# relay.net
KiCad netlist of a schematic drawn in Altium Designer
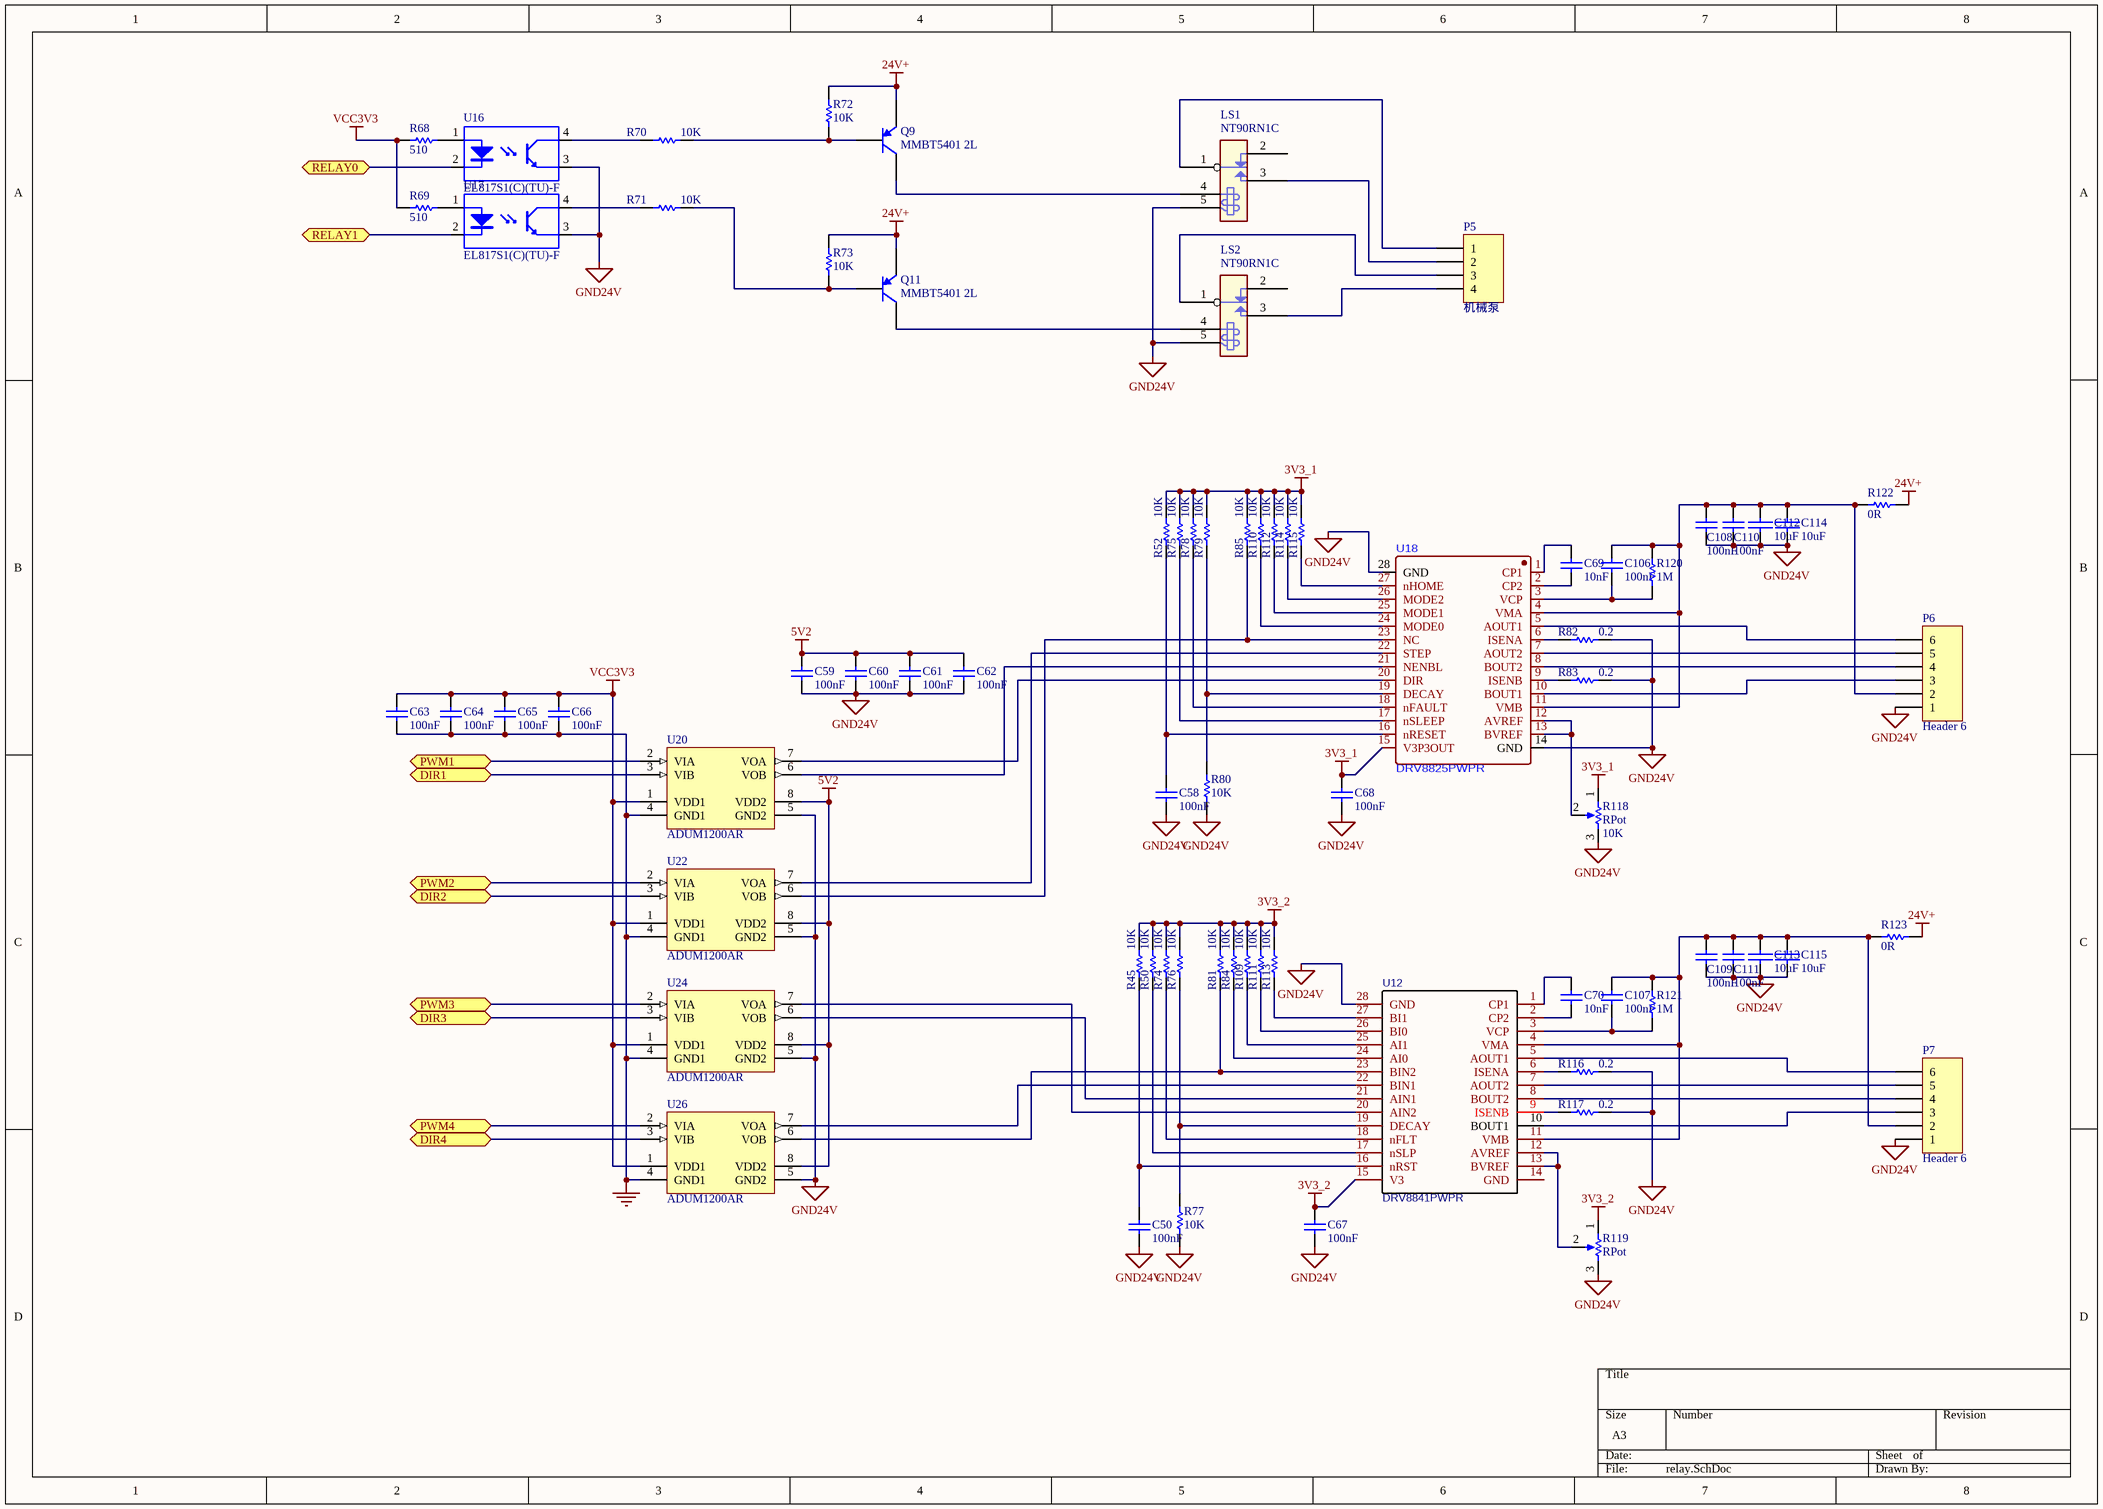
[diagram p0: relay.SchDoc]

(export (version "E")
  (design (tool "Eeschema 10.0.6"))
  (components
    (comp (ref "C50")
      (value "100nF")
      (footprint "0805_C")
      (description "贴片电容")
      (libsource (lib "Miscellaneous Devices LC") (part "0805 100nF(104) 10% 50V"))
    )
    (comp (ref "C58")
      (value "100nF")
      (footprint "0805_C")
      (description "贴片电容")
      (libsource (lib "Miscellaneous Devices LC") (part "0805 100nF(104) 10% 50V"))
    )
    (comp (ref "C59")
      (value "100nF")
      (footprint "0805_C")
      (description "贴片电容")
      (libsource (lib "Miscellaneous Devices LC") (part "0805 100nF(104) 10% 50V"))
    )
    (comp (ref "C60")
      (value "100nF")
      (footprint "0805_C")
      (description "贴片电容")
      (libsource (lib "Miscellaneous Devices LC") (part "0805 100nF(104) 10% 50V"))
    )
    (comp (ref "C61")
      (value "100nF")
      (footprint "0805_C")
      (description "贴片电容")
      (libsource (lib "Miscellaneous Devices LC") (part "0805 100nF(104) 10% 50V"))
    )
    (comp (ref "C62")
      (value "100nF")
      (footprint "0805_C")
      (description "贴片电容")
      (libsource (lib "Miscellaneous Devices LC") (part "0805 100nF(104) 10% 50V"))
    )
    (comp (ref "C63")
      (value "100nF")
      (footprint "0805_C")
      (description "贴片电容")
      (libsource (lib "Miscellaneous Devices LC") (part "0805 100nF(104) 10% 50V"))
    )
    (comp (ref "C64")
      (value "100nF")
      (footprint "0805_C")
      (description "贴片电容")
      (libsource (lib "Miscellaneous Devices LC") (part "0805 100nF(104) 10% 50V"))
    )
    (comp (ref "C65")
      (value "100nF")
      (footprint "0805_C")
      (description "贴片电容")
      (libsource (lib "Miscellaneous Devices LC") (part "0805 100nF(104) 10% 50V"))
    )
    (comp (ref "C66")
      (value "100nF")
      (footprint "0805_C")
      (description "贴片电容")
      (libsource (lib "Miscellaneous Devices LC") (part "0805 100nF(104) 10% 50V"))
    )
    (comp (ref "C67")
      (value "100nF")
      (footprint "0805_C")
      (description "贴片电容")
      (libsource (lib "Miscellaneous Devices LC") (part "0805 100nF(104) 10% 50V"))
    )
    (comp (ref "C68")
      (value "100nF")
      (footprint "0805_C")
      (description "贴片电容")
      (libsource (lib "Miscellaneous Devices LC") (part "0805 100nF(104) 10% 50V"))
    )
    (comp (ref "C69")
      (value "10nF")
      (footprint "0805_C")
      (description "贴片电容")
      (libsource (lib "Miscellaneous Devices LC") (part "0805 100nF(104) 10% 50V"))
    )
    (comp (ref "C70")
      (value "10nF")
      (footprint "0805_C")
      (description "贴片电容")
      (libsource (lib "Miscellaneous Devices LC") (part "0805 100nF(104) 10% 50V"))
    )
    (comp (ref "C106")
      (value "100nF")
      (footprint "0805_C")
      (description "贴片电容")
      (libsource (lib "Miscellaneous Devices LC") (part "0805 100nF(104) 10% 50V"))
    )
    (comp (ref "C107")
      (value "100nF")
      (footprint "0805_C")
      (description "贴片电容")
      (libsource (lib "Miscellaneous Devices LC") (part "0805 100nF(104) 10% 50V"))
    )
    (comp (ref "C108")
      (value "100nF")
      (footprint "0805_C")
      (description "贴片电容")
      (libsource (lib "Miscellaneous Devices LC") (part "0805 100nF(104) 10% 50V"))
    )
    (comp (ref "C109")
      (value "100nF")
      (footprint "0805_C")
      (description "贴片电容")
      (libsource (lib "Miscellaneous Devices LC") (part "0805 100nF(104) 10% 50V"))
    )
    (comp (ref "C110")
      (value "100nF")
      (footprint "0805_C")
      (description "贴片电容")
      (libsource (lib "Miscellaneous Devices LC") (part "0805 100nF(104) 10% 50V"))
    )
    (comp (ref "C111")
      (value "100nF")
      (footprint "0805_C")
      (description "贴片电容")
      (libsource (lib "Miscellaneous Devices LC") (part "0805 100nF(104) 10% 50V"))
    )
    (comp (ref "C112")
      (value "10uF")
      (footprint "0805_C")
      (description "Capacitor")
      (libsource (lib "*") (part "CC"))
    )
    (comp (ref "C113")
      (value "10uF")
      (footprint "0805_C")
      (description "Capacitor")
      (libsource (lib "*") (part "CC"))
    )
    (comp (ref "C114")
      (value "10uF")
      (footprint "0805_C")
      (description "Capacitor")
      (libsource (lib "*") (part "CC"))
    )
    (comp (ref "C115")
      (value "10uF")
      (footprint "0805_C")
      (description "Capacitor")
      (libsource (lib "*") (part "CC"))
    )
    (comp (ref "LS1") (value "NT90RN1C") (libsource (lib "Devices") (part "NT90RN1C")))
    (comp (ref "LS2") (value "NT90RN1C") (libsource (lib "Devices") (part "NT90RN1C")))
    (comp (ref "P5")
      (value "机械泵")
      (footprint "MSTBV 2.5/4-G-5.08")
      (description "Header, 4-Pin, Right Angle")
      (fields (field (name "PUBLISHER") "Altium Limited"))
      (libsource (lib "Miscellaneous Connectors") (part "Header 4H"))
    )
    (comp (ref "P6")
      (value "Header 6")
      (footprint "MC1.5/6-ST-3.81")
      (description "Header, 6-Pin")
      (fields (field (name "PUBLISHER") "Altium Limited"))
      (libsource (lib "Miscellaneous Connectors") (part "Header 6"))
    )
    (comp (ref "P7")
      (value "Header 6")
      (footprint "MC1.5/6-ST-3.81")
      (description "Header, 6-Pin")
      (fields (field (name "PUBLISHER") "Altium Limited"))
      (libsource (lib "Miscellaneous Connectors") (part "Header 6"))
    )
    (comp (ref "Q9")
      (value "MMBT5401 2L")
      (footprint "SOT-23(SOT-23-3)")
      (description "三极管")
      (libsource (lib "Miscellaneous Devices LC") (part "SOT-23 MMBT5401 2L"))
    )
    (comp (ref "Q11")
      (value "MMBT5401 2L")
      (footprint "SOT-23(SOT-23-3)")
      (description "三极管")
      (libsource (lib "Miscellaneous Devices LC") (part "SOT-23 MMBT5401 2L"))
    )
    (comp (ref "R45")
      (value "10K")
      (footprint "0805_R")
      (description "Resistor")
      (fields (field (name "PUBLISHER") "Altium Limited"))
      (libsource (lib "Miscellaneous Devices") (part "Res1"))
    )
    (comp (ref "R50")
      (value "10K")
      (footprint "0805_R")
      (description "Resistor")
      (fields (field (name "PUBLISHER") "Altium Limited"))
      (libsource (lib "Miscellaneous Devices") (part "Res1"))
    )
    (comp (ref "R52")
      (value "10K")
      (footprint "0805_R")
      (description "Resistor")
      (fields (field (name "PUBLISHER") "Altium Limited"))
      (libsource (lib "Miscellaneous Devices") (part "Res1"))
    )
    (comp (ref "R68")
      (value "510")
      (footprint "0805_R")
      (description "Resistor")
      (fields (field (name "PUBLISHER") "Altium Limited"))
      (libsource (lib "Miscellaneous Devices") (part "Res1"))
    )
    (comp (ref "R69")
      (value "510")
      (footprint "0805_R")
      (description "Resistor")
      (fields (field (name "PUBLISHER") "Altium Limited"))
      (libsource (lib "Miscellaneous Devices") (part "Res1"))
    )
    (comp (ref "R70")
      (value "10K")
      (footprint "0805_R")
      (description "Resistor")
      (fields (field (name "PUBLISHER") "Altium Limited"))
      (libsource (lib "Miscellaneous Devices") (part "Res1"))
    )
    (comp (ref "R71")
      (value "10K")
      (footprint "0805_R")
      (description "Resistor")
      (fields (field (name "PUBLISHER") "Altium Limited"))
      (libsource (lib "Miscellaneous Devices") (part "Res1"))
    )
    (comp (ref "R72")
      (value "10K")
      (footprint "0805_R")
      (description "Resistor")
      (fields (field (name "PUBLISHER") "Altium Limited"))
      (libsource (lib "Miscellaneous Devices") (part "Res1"))
    )
    (comp (ref "R73")
      (value "10K")
      (footprint "0805_R")
      (description "Resistor")
      (fields (field (name "PUBLISHER") "Altium Limited"))
      (libsource (lib "Miscellaneous Devices") (part "Res1"))
    )
    (comp (ref "R74")
      (value "10K")
      (footprint "0805_R")
      (description "Resistor")
      (fields (field (name "PUBLISHER") "Altium Limited"))
      (libsource (lib "Miscellaneous Devices") (part "Res1"))
    )
    (comp (ref "R75")
      (value "10K")
      (footprint "0805_R")
      (description "Resistor")
      (fields (field (name "PUBLISHER") "Altium Limited"))
      (libsource (lib "Miscellaneous Devices") (part "Res1"))
    )
    (comp (ref "R76")
      (value "10K")
      (footprint "0805_R")
      (description "Resistor")
      (fields (field (name "PUBLISHER") "Altium Limited"))
      (libsource (lib "Miscellaneous Devices") (part "Res1"))
    )
    (comp (ref "R77")
      (value "10K")
      (footprint "0805_R")
      (description "Resistor")
      (fields (field (name "PUBLISHER") "Altium Limited"))
      (libsource (lib "Miscellaneous Devices") (part "Res1"))
    )
    (comp (ref "R78")
      (value "10K")
      (footprint "0805_R")
      (description "Resistor")
      (fields (field (name "PUBLISHER") "Altium Limited"))
      (libsource (lib "Miscellaneous Devices") (part "Res1"))
    )
    (comp (ref "R79")
      (value "10K")
      (footprint "0805_R")
      (description "Resistor")
      (fields (field (name "PUBLISHER") "Altium Limited"))
      (libsource (lib "Miscellaneous Devices") (part "Res1"))
    )
    (comp (ref "R80")
      (value "10K")
      (footprint "0805_R")
      (description "Resistor")
      (fields (field (name "PUBLISHER") "Altium Limited"))
      (libsource (lib "Miscellaneous Devices") (part "Res1"))
    )
    (comp (ref "R81")
      (value "10K")
      (footprint "0805_R")
      (description "Resistor")
      (fields (field (name "PUBLISHER") "Altium Limited"))
      (libsource (lib "Miscellaneous Devices") (part "Res1"))
    )
    (comp (ref "R82")
      (value "0.2")
      (footprint "R1210")
      (description "Resistor")
      (fields (field (name "PUBLISHER") "Altium Limited"))
      (libsource (lib "Miscellaneous Devices") (part "Res1"))
    )
    (comp (ref "R83")
      (value "0.2")
      (footprint "R1210")
      (description "Resistor")
      (fields (field (name "PUBLISHER") "Altium Limited"))
      (libsource (lib "Miscellaneous Devices") (part "Res1"))
    )
    (comp (ref "R84")
      (value "10K")
      (footprint "0805_R")
      (description "Resistor")
      (fields (field (name "PUBLISHER") "Altium Limited"))
      (libsource (lib "Miscellaneous Devices") (part "Res1"))
    )
    (comp (ref "R85")
      (value "10K")
      (footprint "0805_R")
      (description "Resistor")
      (fields (field (name "PUBLISHER") "Altium Limited"))
      (libsource (lib "Miscellaneous Devices") (part "Res1"))
    )
    (comp (ref "R109")
      (value "10K")
      (footprint "0805_R")
      (description "Resistor")
      (fields (field (name "PUBLISHER") "Altium Limited"))
      (libsource (lib "Miscellaneous Devices") (part "Res1"))
    )
    (comp (ref "R110")
      (value "10K")
      (footprint "0805_R")
      (description "Resistor")
      (fields (field (name "PUBLISHER") "Altium Limited"))
      (libsource (lib "Miscellaneous Devices") (part "Res1"))
    )
    (comp (ref "R111")
      (value "10K")
      (footprint "0805_R")
      (description "Resistor")
      (fields (field (name "PUBLISHER") "Altium Limited"))
      (libsource (lib "Miscellaneous Devices") (part "Res1"))
    )
    (comp (ref "R112")
      (value "10K")
      (footprint "0805_R")
      (description "Resistor")
      (fields (field (name "PUBLISHER") "Altium Limited"))
      (libsource (lib "Miscellaneous Devices") (part "Res1"))
    )
    (comp (ref "R113")
      (value "10K")
      (footprint "0805_R")
      (description "Resistor")
      (fields (field (name "PUBLISHER") "Altium Limited"))
      (libsource (lib "Miscellaneous Devices") (part "Res1"))
    )
    (comp (ref "R114")
      (value "10K")
      (footprint "0805_R")
      (description "Resistor")
      (fields (field (name "PUBLISHER") "Altium Limited"))
      (libsource (lib "Miscellaneous Devices") (part "Res1"))
    )
    (comp (ref "R115")
      (value "10K")
      (footprint "0805_R")
      (description "Resistor")
      (fields (field (name "PUBLISHER") "Altium Limited"))
      (libsource (lib "Miscellaneous Devices") (part "Res1"))
    )
    (comp (ref "R116")
      (value "0.2")
      (footprint "R1210")
      (description "Resistor")
      (fields (field (name "PUBLISHER") "Altium Limited"))
      (libsource (lib "Miscellaneous Devices") (part "Res1"))
    )
    (comp (ref "R117")
      (value "0.2")
      (footprint "R1210")
      (description "Resistor")
      (fields (field (name "PUBLISHER") "Altium Limited"))
      (libsource (lib "Miscellaneous Devices") (part "Res1"))
    )
    (comp (ref "R118")
      (value "RPot")
      (footprint "RES-ADJ-TH_3362P")
      (description "Potentiometer")
      (fields (field (name "ALTIUM_VALUE") "10K") (field (name "PUBLISHER") "Altium Limited"))
      (libsource (lib "Miscellaneous Devices") (part "RPot"))
    )
    (comp (ref "R119")
      (value "RPot")
      (footprint "RES-ADJ-TH_3362P")
      (description "Potentiometer")
      (fields (field (name "PUBLISHER") "Altium Limited"))
      (libsource (lib "Miscellaneous Devices") (part "RPot"))
    )
    (comp (ref "R120")
      (value "1M")
      (footprint "0805_R")
      (description "Resistor")
      (fields (field (name "PUBLISHER") "Altium Limited"))
      (libsource (lib "Miscellaneous Devices") (part "Res1"))
    )
    (comp (ref "R121")
      (value "1M")
      (footprint "0805_R")
      (description "Resistor")
      (fields (field (name "PUBLISHER") "Altium Limited"))
      (libsource (lib "Miscellaneous Devices") (part "Res1"))
    )
    (comp (ref "R122")
      (value "0R")
      (footprint "0805_R")
      (description "Resistor")
      (fields (field (name "PUBLISHER") "Altium Limited"))
      (libsource (lib "Miscellaneous Devices") (part "Res1"))
    )
    (comp (ref "R123")
      (value "0R")
      (footprint "0805_R")
      (description "Resistor")
      (fields (field (name "PUBLISHER") "Altium Limited"))
      (libsource (lib "Miscellaneous Devices") (part "Res1"))
    )
    (comp (ref "U12")
      (value "DRV8841PWPR")
      (footprint "HTSSOP-28_L9.8-W4.5-P0.65-LS6.6-BL-EP")
      (fields (field (name "BOM_SUPPLIER PART") "C36542"))
      (libsource (lib "IC") (part "DRV8841PWPR"))
    )
    (comp (ref "U16")
      (value "EL817S1(C)(TU)-F")
      (footprint "LC-SMD-4")
      (libsource (lib "IC") (part "TLP521"))
    )
    (comp (ref "U17")
      (value "EL817S1(C)(TU)-F")
      (footprint "LC-SMD-4")
      (libsource (lib "IC") (part "TLP521"))
    )
    (comp (ref "U18")
      (value "DRV8825PWPR")
      (footprint "HTSSOP_24P_L10.0-W4.4-P0.65-BL-EP")
      (libsource (lib "altium-import") (part "root_0_mirrored_DRV8825PWPR_"))
    )
    (comp (ref "U20")
      (value "ADUM1200AR")
      (footprint "ADI-R-8_N")
      (fields (field (name "MANUFACTURER") "Analog Devices"))
      (libsource (lib "Analog Devices Interface and Isolation Digital Isolators") (part "ADUM1200AR"))
    )
    (comp (ref "U22")
      (value "ADUM1200AR")
      (footprint "ADI-R-8_N")
      (fields (field (name "MANUFACTURER") "Analog Devices"))
      (libsource (lib "Analog Devices Interface and Isolation Digital Isolators") (part "ADUM1200AR"))
    )
    (comp (ref "U24")
      (value "ADUM1200AR")
      (footprint "ADI-R-8_N")
      (fields (field (name "MANUFACTURER") "Analog Devices"))
      (libsource (lib "Analog Devices Interface and Isolation Digital Isolators") (part "ADUM1200AR"))
    )
    (comp (ref "U26")
      (value "ADUM1200AR")
      (footprint "ADI-R-8_N")
      (fields (field (name "MANUFACTURER") "Analog Devices"))
      (libsource (lib "Analog Devices Interface and Isolation Digital Isolators") (part "ADUM1200AR"))
    )
  )
  (nets
    (net (code "1") (name "/DIR1") (class "Default")
      (node (ref "U20") (pin "3") (pinfunction "VIB_3") (pintype "input"))
    )
    (net (code "2") (name "/DIR2") (class "Default")
      (node (ref "U22") (pin "3") (pinfunction "VIB_3") (pintype "input"))
    )
    (net (code "3") (name "/DIR3") (class "Default")
      (node (ref "U24") (pin "3") (pinfunction "VIB_3") (pintype "input"))
    )
    (net (code "4") (name "/DIR4") (class "Default")
      (node (ref "U26") (pin "3") (pinfunction "VIB_3") (pintype "input"))
    )
    (net (code "5") (name "/PWM1") (class "Default")
      (node (ref "U20") (pin "2") (pinfunction "VIA_2") (pintype "input"))
    )
    (net (code "6") (name "/PWM2") (class "Default")
      (node (ref "U22") (pin "2") (pinfunction "VIA_2") (pintype "input"))
    )
    (net (code "7") (name "/PWM3") (class "Default")
      (node (ref "U24") (pin "2") (pinfunction "VIA_2") (pintype "input"))
    )
    (net (code "8") (name "/PWM4") (class "Default")
      (node (ref "U26") (pin "2") (pinfunction "VIA_2") (pintype "input"))
    )
    (net (code "9") (name "/RELAY0") (class "Default")
      (node (ref "U16") (pin "2") (pinfunction "K_2") (pintype "passive"))
    )
    (net (code "10") (name "/RELAY1") (class "Default")
      (node (ref "U17") (pin "2") (pinfunction "K_2") (pintype "passive"))
    )
    (net (code "11") (name "3V3_1") (class "Default")
      (node (ref "C68") (pin "1") (pinfunction "1_1") (pintype "passive"))
      (node (ref "R110") (pin "1") (pinfunction "1_1") (pintype "passive"))
      (node (ref "R112") (pin "1") (pinfunction "1_1") (pintype "passive"))
      (node (ref "R114") (pin "1") (pinfunction "1_1") (pintype "passive"))
      (node (ref "R115") (pin "1") (pinfunction "1_1") (pintype "passive"))
      (node (ref "R118") (pin "1") (pinfunction "TOP_1") (pintype "passive"))
      (node (ref "R52") (pin "1") (pinfunction "1_1") (pintype "passive"))
      (node (ref "R75") (pin "1") (pinfunction "1_1") (pintype "passive"))
      (node (ref "R78") (pin "1") (pinfunction "1_1") (pintype "passive"))
      (node (ref "R79") (pin "1") (pinfunction "1_1") (pintype "passive"))
      (node (ref "R85") (pin "1") (pinfunction "1_1") (pintype "passive"))
      (node (ref "U18") (pin "15") (pinfunction "V3P3OUT_15") (pintype "passive"))
    )
    (net (code "12") (name "3V3_2") (class "Default")
      (node (ref "C67") (pin "1") (pinfunction "1_1") (pintype "passive"))
      (node (ref "R109") (pin "1") (pinfunction "1_1") (pintype "passive"))
      (node (ref "R111") (pin "1") (pinfunction "1_1") (pintype "passive"))
      (node (ref "R113") (pin "1") (pinfunction "1_1") (pintype "passive"))
      (node (ref "R119") (pin "1") (pinfunction "TOP_1") (pintype "passive"))
      (node (ref "R45") (pin "1") (pinfunction "1_1") (pintype "passive"))
      (node (ref "R50") (pin "1") (pinfunction "1_1") (pintype "passive"))
      (node (ref "R74") (pin "1") (pinfunction "1_1") (pintype "passive"))
      (node (ref "R76") (pin "1") (pinfunction "1_1") (pintype "passive"))
      (node (ref "R81") (pin "1") (pinfunction "1_1") (pintype "passive"))
      (node (ref "R84") (pin "1") (pinfunction "1_1") (pintype "passive"))
      (node (ref "U12") (pin "15") (pinfunction "V3_15") (pintype "passive"))
    )
    (net (code "13") (name "5V2") (class "Default")
      (node (ref "C59") (pin "2") (pinfunction "2_2") (pintype "passive"))
      (node (ref "C60") (pin "2") (pinfunction "2_2") (pintype "passive"))
      (node (ref "C61") (pin "2") (pinfunction "2_2") (pintype "passive"))
      (node (ref "C62") (pin "2") (pinfunction "2_2") (pintype "passive"))
      (node (ref "U20") (pin "8") (pinfunction "VDD2_8") (pintype "power_in"))
      (node (ref "U22") (pin "8") (pinfunction "VDD2_8") (pintype "power_in"))
      (node (ref "U24") (pin "8") (pinfunction "VDD2_8") (pintype "power_in"))
      (node (ref "U26") (pin "8") (pinfunction "VDD2_8") (pintype "power_in"))
    )
    (net (code "14") (name "24V+") (class "Default")
      (node (ref "Q11") (pin "2") (pinfunction "E_2") (pintype "passive"))
      (node (ref "Q9") (pin "2") (pinfunction "E_2") (pintype "passive"))
      (node (ref "R122") (pin "2") (pinfunction "2_2") (pintype "passive"))
      (node (ref "R123") (pin "2") (pinfunction "2_2") (pintype "passive"))
      (node (ref "R72") (pin "2") (pinfunction "2_2") (pintype "passive"))
      (node (ref "R73") (pin "2") (pinfunction "2_2") (pintype "passive"))
    )
    (net (code "15") (name "GND") (class "Default")
      (node (ref "C63") (pin "1") (pinfunction "1_1") (pintype "passive"))
      (node (ref "C64") (pin "1") (pinfunction "1_1") (pintype "passive"))
      (node (ref "C65") (pin "1") (pinfunction "1_1") (pintype "passive"))
      (node (ref "C66") (pin "1") (pinfunction "1_1") (pintype "passive"))
      (node (ref "U20") (pin "4") (pinfunction "GND1_4") (pintype "power_in"))
      (node (ref "U22") (pin "4") (pinfunction "GND1_4") (pintype "power_in"))
      (node (ref "U24") (pin "4") (pinfunction "GND1_4") (pintype "power_in"))
      (node (ref "U26") (pin "4") (pinfunction "GND1_4") (pintype "power_in"))
    )
    (net (code "16") (name "GND24V") (class "Default")
      (node (ref "C108") (pin "1") (pinfunction "1_1") (pintype "passive"))
      (node (ref "C109") (pin "1") (pinfunction "1_1") (pintype "passive"))
      (node (ref "C110") (pin "1") (pinfunction "1_1") (pintype "passive"))
      (node (ref "C111") (pin "1") (pinfunction "1_1") (pintype "passive"))
      (node (ref "C112") (pin "1") (pinfunction "1_1") (pintype "passive"))
      (node (ref "C113") (pin "1") (pinfunction "1_1") (pintype "passive"))
      (node (ref "C114") (pin "1") (pinfunction "1_1") (pintype "passive"))
      (node (ref "C115") (pin "1") (pinfunction "1_1") (pintype "passive"))
      (node (ref "C50") (pin "2") (pinfunction "2_2") (pintype "passive"))
      (node (ref "C58") (pin "2") (pinfunction "2_2") (pintype "passive"))
      (node (ref "C59") (pin "1") (pinfunction "1_1") (pintype "passive"))
      (node (ref "C60") (pin "1") (pinfunction "1_1") (pintype "passive"))
      (node (ref "C61") (pin "1") (pinfunction "1_1") (pintype "passive"))
      (node (ref "C62") (pin "1") (pinfunction "1_1") (pintype "passive"))
      (node (ref "C67") (pin "2") (pinfunction "2_2") (pintype "passive"))
      (node (ref "C68") (pin "2") (pinfunction "2_2") (pintype "passive"))
      (node (ref "LS1") (pin "5") (pinfunction "COIL2_5") (pintype "passive"))
      (node (ref "LS2") (pin "5") (pinfunction "COIL2_5") (pintype "passive"))
      (node (ref "P6") (pin "1") (pinfunction "1_1") (pintype "passive"))
      (node (ref "P7") (pin "1") (pinfunction "1_1") (pintype "passive"))
      (node (ref "R116") (pin "1") (pinfunction "1_1") (pintype "passive"))
      (node (ref "R117") (pin "1") (pinfunction "1_1") (pintype "passive"))
      (node (ref "R118") (pin "3") (pinfunction "BOT_3") (pintype "passive"))
      (node (ref "R119") (pin "3") (pinfunction "BOT_3") (pintype "passive"))
      (node (ref "R77") (pin "2") (pinfunction "2_2") (pintype "passive"))
      (node (ref "R80") (pin "2") (pinfunction "2_2") (pintype "passive"))
      (node (ref "R82") (pin "1") (pinfunction "1_1") (pintype "passive"))
      (node (ref "R83") (pin "1") (pinfunction "1_1") (pintype "passive"))
      (node (ref "U12") (pin "28") (pinfunction "GND_28") (pintype "passive"))
      (node (ref "U16") (pin "3") (pinfunction "E_3") (pintype "passive"))
      (node (ref "U17") (pin "3") (pinfunction "E_3") (pintype "passive"))
      (node (ref "U18") (pin "14") (pinfunction "GND_14") (pintype "passive"))
      (node (ref "U18") (pin "28") (pinfunction "GND_28") (pintype "passive"))
      (node (ref "U20") (pin "5") (pinfunction "GND2_5") (pintype "power_in"))
      (node (ref "U22") (pin "5") (pinfunction "GND2_5") (pintype "power_in"))
      (node (ref "U24") (pin "5") (pinfunction "GND2_5") (pintype "power_in"))
      (node (ref "U26") (pin "5") (pinfunction "GND2_5") (pintype "power_in"))
    )
    (net (code "17") (name "Net-(LS1-COIL1)") (class "Default")
      (node (ref "LS1") (pin "4") (pinfunction "COIL1_4") (pintype "passive"))
      (node (ref "Q9") (pin "3") (pinfunction "C_3") (pintype "passive"))
    )
    (net (code "18") (name "Net-(LS1-COMMON)") (class "Default")
      (node (ref "LS1") (pin "1") (pinfunction "COMMON_1") (pintype "passive"))
      (node (ref "P5") (pin "1") (pinfunction "1_1") (pintype "passive"))
    )
    (net (code "19") (name "Net-(LS1-NO)") (class "Default")
      (node (ref "LS1") (pin "3") (pinfunction "NO_3") (pintype "passive"))
      (node (ref "P5") (pin "2") (pinfunction "2_2") (pintype "passive"))
    )
    (net (code "20") (name "Net-(LS2-COIL1)") (class "Default")
      (node (ref "LS2") (pin "4") (pinfunction "COIL1_4") (pintype "passive"))
      (node (ref "Q11") (pin "3") (pinfunction "C_3") (pintype "passive"))
    )
    (net (code "21") (name "Net-(LS2-COMMON)") (class "Default")
      (node (ref "LS2") (pin "1") (pinfunction "COMMON_1") (pintype "passive"))
      (node (ref "P5") (pin "3") (pinfunction "3_3") (pintype "passive"))
    )
    (net (code "22") (name "Net-(LS2-NO)") (class "Default")
      (node (ref "LS2") (pin "3") (pinfunction "NO_3") (pintype "passive"))
      (node (ref "P5") (pin "4") (pinfunction "4_4") (pintype "passive"))
    )
    (net (code "23") (name "Net-(Q9-B)") (class "Default")
      (node (ref "Q9") (pin "1") (pinfunction "B_1") (pintype "passive"))
      (node (ref "R70") (pin "2") (pinfunction "2_2") (pintype "passive"))
      (node (ref "R72") (pin "1") (pinfunction "1_1") (pintype "passive"))
    )
    (net (code "24") (name "Net-(Q11-B)") (class "Default")
      (node (ref "Q11") (pin "1") (pinfunction "B_1") (pintype "passive"))
      (node (ref "R71") (pin "2") (pinfunction "2_2") (pintype "passive"))
      (node (ref "R73") (pin "1") (pinfunction "1_1") (pintype "passive"))
    )
    (net (code "25") (name "Net-(R118-TAP)") (class "Default")
      (node (ref "R118") (pin "2") (pinfunction "TAP_2") (pintype "passive"))
      (node (ref "U18") (pin "12") (pinfunction "AVREF_12") (pintype "passive"))
      (node (ref "U18") (pin "13") (pinfunction "BVREF_13") (pintype "passive"))
    )
    (net (code "26") (name "Net-(R119-TAP)") (class "Default")
      (node (ref "R119") (pin "2") (pinfunction "TAP_2") (pintype "passive"))
      (node (ref "U12") (pin "12") (pinfunction "AVREF_12") (pintype "passive"))
      (node (ref "U12") (pin "13") (pinfunction "BVREF_13") (pintype "passive"))
    )
    (net (code "27") (name "Net-(U12-AI0)") (class "Default")
      (node (ref "R84") (pin "2") (pinfunction "2_2") (pintype "passive"))
      (node (ref "U12") (pin "24") (pinfunction "AI0_24") (pintype "passive"))
    )
    (net (code "28") (name "Net-(U12-AI1)") (class "Default")
      (node (ref "R109") (pin "2") (pinfunction "2_2") (pintype "passive"))
      (node (ref "U12") (pin "25") (pinfunction "AI1_25") (pintype "passive"))
    )
    (net (code "29") (name "Net-(U12-AIN1)") (class "Default")
      (node (ref "U12") (pin "21") (pinfunction "AIN1_21") (pintype "passive"))
      (node (ref "U24") (pin "6") (pinfunction "VOB_6") (pintype "output"))
    )
    (net (code "30") (name "Net-(U12-AIN2)") (class "Default")
      (node (ref "U12") (pin "20") (pinfunction "AIN2_20") (pintype "passive"))
      (node (ref "U24") (pin "7") (pinfunction "VOA_7") (pintype "output"))
    )
    (net (code "31") (name "Net-(U12-AOUT1)") (class "Default")
      (node (ref "P7") (pin "6") (pinfunction "6_6") (pintype "passive"))
      (node (ref "U12") (pin "5") (pinfunction "AOUT1_5") (pintype "passive"))
    )
    (net (code "32") (name "Net-(U12-AOUT2)") (class "Default")
      (node (ref "P7") (pin "5") (pinfunction "5_5") (pintype "passive"))
      (node (ref "U12") (pin "7") (pinfunction "AOUT2_7") (pintype "passive"))
    )
    (net (code "33") (name "Net-(U12-BI0)") (class "Default")
      (node (ref "R111") (pin "2") (pinfunction "2_2") (pintype "passive"))
      (node (ref "U12") (pin "26") (pinfunction "BI0_26") (pintype "passive"))
    )
    (net (code "34") (name "Net-(U12-BI1)") (class "Default")
      (node (ref "R113") (pin "2") (pinfunction "2_2") (pintype "passive"))
      (node (ref "U12") (pin "27") (pinfunction "BI1_27") (pintype "passive"))
    )
    (net (code "35") (name "Net-(U12-BIN1)") (class "Default")
      (node (ref "U12") (pin "22") (pinfunction "BIN1_22") (pintype "passive"))
      (node (ref "U26") (pin "7") (pinfunction "VOA_7") (pintype "output"))
    )
    (net (code "36") (name "Net-(U12-BIN2)") (class "Default")
      (node (ref "R81") (pin "2") (pinfunction "2_2") (pintype "passive"))
      (node (ref "U12") (pin "23") (pinfunction "BIN2_23") (pintype "passive"))
      (node (ref "U26") (pin "6") (pinfunction "VOB_6") (pintype "output"))
    )
    (net (code "37") (name "Net-(U12-BOUT1)") (class "Default")
      (node (ref "P7") (pin "3") (pinfunction "3_3") (pintype "passive"))
      (node (ref "U12") (pin "10") (pinfunction "BOUT1_10") (pintype "passive"))
    )
    (net (code "38") (name "Net-(U12-BOUT2)") (class "Default")
      (node (ref "P7") (pin "4") (pinfunction "4_4") (pintype "passive"))
      (node (ref "U12") (pin "8") (pinfunction "BOUT2_8") (pintype "passive"))
    )
    (net (code "39") (name "Net-(U12-CP1)") (class "Default")
      (node (ref "C70") (pin "1") (pinfunction "1_1") (pintype "passive"))
      (node (ref "U12") (pin "1") (pinfunction "CP1_1") (pintype "passive"))
    )
    (net (code "40") (name "Net-(U12-CP2)") (class "Default")
      (node (ref "C70") (pin "2") (pinfunction "2_2") (pintype "passive"))
      (node (ref "U12") (pin "2") (pinfunction "CP2_2") (pintype "passive"))
    )
    (net (code "41") (name "Net-(U12-DECAY)") (class "Default")
      (node (ref "R76") (pin "2") (pinfunction "2_2") (pintype "passive"))
      (node (ref "R77") (pin "1") (pinfunction "1_1") (pintype "passive"))
      (node (ref "U12") (pin "19") (pinfunction "DECAY_19") (pintype "passive"))
    )
    (net (code "42") (name "Net-(U12-ISENA)") (class "Default")
      (node (ref "R116") (pin "2") (pinfunction "2_2") (pintype "passive"))
      (node (ref "U12") (pin "6") (pinfunction "ISENA_6") (pintype "passive"))
    )
    (net (code "43") (name "Net-(U12-ISENB)") (class "Default")
      (node (ref "R117") (pin "2") (pinfunction "2_2") (pintype "passive"))
      (node (ref "U12") (pin "9") (pinfunction "ISENB_9") (pintype "passive"))
    )
    (net (code "44") (name "Net-(U12-VCP)") (class "Default")
      (node (ref "C107") (pin "1") (pinfunction "1_1") (pintype "passive"))
      (node (ref "R121") (pin "2") (pinfunction "2_2") (pintype "passive"))
      (node (ref "U12") (pin "3") (pinfunction "VCP_3") (pintype "passive"))
    )
    (net (code "45") (name "Net-(U12-VMA)") (class "Default")
      (node (ref "C107") (pin "2") (pinfunction "2_2") (pintype "passive"))
      (node (ref "C109") (pin "2") (pinfunction "2_2") (pintype "passive"))
      (node (ref "C111") (pin "2") (pinfunction "2_2") (pintype "passive"))
      (node (ref "C113") (pin "2") (pinfunction "2_2") (pintype "passive"))
      (node (ref "C115") (pin "2") (pinfunction "2_2") (pintype "passive"))
      (node (ref "P7") (pin "2") (pinfunction "2_2") (pintype "passive"))
      (node (ref "R121") (pin "1") (pinfunction "1_1") (pintype "passive"))
      (node (ref "R123") (pin "1") (pinfunction "1_1") (pintype "passive"))
      (node (ref "U12") (pin "11") (pinfunction "VMB_11") (pintype "passive"))
      (node (ref "U12") (pin "4") (pinfunction "VMA_4") (pintype "passive"))
    )
    (net (code "46") (name "Net-(U12-nFLT)") (class "Default")
      (node (ref "R74") (pin "2") (pinfunction "2_2") (pintype "passive"))
      (node (ref "U12") (pin "18") (pinfunction "nFLT_18") (pintype "passive"))
    )
    (net (code "47") (name "Net-(U12-nRST)") (class "Default")
      (node (ref "C50") (pin "1") (pinfunction "1_1") (pintype "passive"))
      (node (ref "R45") (pin "2") (pinfunction "2_2") (pintype "passive"))
      (node (ref "U12") (pin "16") (pinfunction "nRST_16") (pintype "passive"))
    )
    (net (code "48") (name "Net-(U12-nSLP)") (class "Default")
      (node (ref "R50") (pin "2") (pinfunction "2_2") (pintype "passive"))
      (node (ref "U12") (pin "17") (pinfunction "nSLP_17") (pintype "passive"))
    )
    (net (code "49") (name "Net-(U16-A)") (class "Default")
      (node (ref "R68") (pin "1") (pinfunction "1_1") (pintype "passive"))
      (node (ref "U16") (pin "1") (pinfunction "A_1") (pintype "passive"))
    )
    (net (code "50") (name "Net-(U16-C)") (class "Default")
      (node (ref "R70") (pin "1") (pinfunction "1_1") (pintype "passive"))
      (node (ref "U16") (pin "4") (pinfunction "C_4") (pintype "passive"))
    )
    (net (code "51") (name "Net-(U17-A)") (class "Default")
      (node (ref "R69") (pin "1") (pinfunction "1_1") (pintype "passive"))
      (node (ref "U17") (pin "1") (pinfunction "A_1") (pintype "passive"))
    )
    (net (code "52") (name "Net-(U17-C)") (class "Default")
      (node (ref "R71") (pin "1") (pinfunction "1_1") (pintype "passive"))
      (node (ref "U17") (pin "4") (pinfunction "C_4") (pintype "passive"))
    )
    (net (code "53") (name "Net-(U18-AOUT1)") (class "Default")
      (node (ref "P6") (pin "6") (pinfunction "6_6") (pintype "passive"))
      (node (ref "U18") (pin "5") (pinfunction "AOUT1_5") (pintype "passive"))
    )
    (net (code "54") (name "Net-(U18-AOUT2)") (class "Default")
      (node (ref "P6") (pin "5") (pinfunction "5_5") (pintype "passive"))
      (node (ref "U18") (pin "7") (pinfunction "AOUT2_7") (pintype "passive"))
    )
    (net (code "55") (name "Net-(U18-BOUT1)") (class "Default")
      (node (ref "P6") (pin "3") (pinfunction "3_3") (pintype "passive"))
      (node (ref "U18") (pin "10") (pinfunction "BOUT1_10") (pintype "passive"))
    )
    (net (code "56") (name "Net-(U18-BOUT2)") (class "Default")
      (node (ref "P6") (pin "4") (pinfunction "4_4") (pintype "passive"))
      (node (ref "U18") (pin "8") (pinfunction "BOUT2_8") (pintype "passive"))
    )
    (net (code "57") (name "Net-(U18-CP1)") (class "Default")
      (node (ref "C69") (pin "1") (pinfunction "1_1") (pintype "passive"))
      (node (ref "U18") (pin "1") (pinfunction "CP1_1") (pintype "passive"))
    )
    (net (code "58") (name "Net-(U18-CP2)") (class "Default")
      (node (ref "C69") (pin "2") (pinfunction "2_2") (pintype "passive"))
      (node (ref "U18") (pin "2") (pinfunction "CP2_2") (pintype "passive"))
    )
    (net (code "59") (name "Net-(U18-DECAY)") (class "Default")
      (node (ref "R79") (pin "2") (pinfunction "2_2") (pintype "passive"))
      (node (ref "R80") (pin "1") (pinfunction "1_1") (pintype "passive"))
      (node (ref "U18") (pin "19") (pinfunction "DECAY_19") (pintype "passive"))
    )
    (net (code "60") (name "Net-(U18-DIR)") (class "Default")
      (node (ref "U18") (pin "20") (pinfunction "DIR_20") (pintype "passive"))
      (node (ref "U20") (pin "7") (pinfunction "VOA_7") (pintype "output"))
    )
    (net (code "61") (name "Net-(U18-ISENA)") (class "Default")
      (node (ref "R82") (pin "2") (pinfunction "2_2") (pintype "passive"))
      (node (ref "U18") (pin "6") (pinfunction "ISENA_6") (pintype "passive"))
    )
    (net (code "62") (name "Net-(U18-ISENB)") (class "Default")
      (node (ref "R83") (pin "2") (pinfunction "2_2") (pintype "passive"))
      (node (ref "U18") (pin "9") (pinfunction "ISENB_9") (pintype "passive"))
    )
    (net (code "63") (name "Net-(U18-MODE0)") (class "Default")
      (node (ref "R110") (pin "2") (pinfunction "2_2") (pintype "passive"))
      (node (ref "U18") (pin "24") (pinfunction "MODE0_24") (pintype "passive"))
    )
    (net (code "64") (name "Net-(U18-MODE1)") (class "Default")
      (node (ref "R112") (pin "2") (pinfunction "2_2") (pintype "passive"))
      (node (ref "U18") (pin "25") (pinfunction "MODE1_25") (pintype "passive"))
    )
    (net (code "65") (name "Net-(U18-MODE2)") (class "Default")
      (node (ref "R114") (pin "2") (pinfunction "2_2") (pintype "passive"))
      (node (ref "U18") (pin "26") (pinfunction "MODE2_26") (pintype "passive"))
    )
    (net (code "66") (name "Net-(U18-NC)") (class "Default")
      (node (ref "R85") (pin "2") (pinfunction "2_2") (pintype "passive"))
      (node (ref "U18") (pin "23") (pinfunction "NC_23") (pintype "passive"))
      (node (ref "U22") (pin "6") (pinfunction "VOB_6") (pintype "output"))
    )
    (net (code "67") (name "Net-(U18-NENBL)") (class "Default")
      (node (ref "U18") (pin "21") (pinfunction "NENBL_21") (pintype "passive"))
      (node (ref "U20") (pin "6") (pinfunction "VOB_6") (pintype "output"))
    )
    (net (code "68") (name "Net-(U18-STEP)") (class "Default")
      (node (ref "U18") (pin "22") (pinfunction "STEP_22") (pintype "passive"))
      (node (ref "U22") (pin "7") (pinfunction "VOA_7") (pintype "output"))
    )
    (net (code "69") (name "Net-(U18-VCP)") (class "Default")
      (node (ref "C106") (pin "1") (pinfunction "1_1") (pintype "passive"))
      (node (ref "R120") (pin "2") (pinfunction "2_2") (pintype "passive"))
      (node (ref "U18") (pin "3") (pinfunction "VCP_3") (pintype "passive"))
    )
    (net (code "70") (name "Net-(U18-VMA)") (class "Default")
      (node (ref "C106") (pin "2") (pinfunction "2_2") (pintype "passive"))
      (node (ref "C108") (pin "2") (pinfunction "2_2") (pintype "passive"))
      (node (ref "C110") (pin "2") (pinfunction "2_2") (pintype "passive"))
      (node (ref "C112") (pin "2") (pinfunction "2_2") (pintype "passive"))
      (node (ref "C114") (pin "2") (pinfunction "2_2") (pintype "passive"))
      (node (ref "P6") (pin "2") (pinfunction "2_2") (pintype "passive"))
      (node (ref "R120") (pin "1") (pinfunction "1_1") (pintype "passive"))
      (node (ref "R122") (pin "1") (pinfunction "1_1") (pintype "passive"))
      (node (ref "U18") (pin "11") (pinfunction "VMB_11") (pintype "passive"))
      (node (ref "U18") (pin "4") (pinfunction "VMA_4") (pintype "passive"))
    )
    (net (code "71") (name "Net-(U18-nFAULT)") (class "Default")
      (node (ref "R78") (pin "2") (pinfunction "2_2") (pintype "passive"))
      (node (ref "U18") (pin "18") (pinfunction "nFAULT_18") (pintype "passive"))
    )
    (net (code "72") (name "Net-(U18-nHOME)") (class "Default")
      (node (ref "R115") (pin "2") (pinfunction "2_2") (pintype "passive"))
      (node (ref "U18") (pin "27") (pinfunction "nHOME_27") (pintype "passive"))
    )
    (net (code "73") (name "Net-(U18-nRESET)") (class "Default")
      (node (ref "C58") (pin "1") (pinfunction "1_1") (pintype "passive"))
      (node (ref "R52") (pin "2") (pinfunction "2_2") (pintype "passive"))
      (node (ref "U18") (pin "16") (pinfunction "nRESET_16") (pintype "passive"))
    )
    (net (code "74") (name "Net-(U18-nSLEEP)") (class "Default")
      (node (ref "R75") (pin "2") (pinfunction "2_2") (pintype "passive"))
      (node (ref "U18") (pin "17") (pinfunction "nSLEEP_17") (pintype "passive"))
    )
    (net (code "75") (name "VCC3V3") (class "Default")
      (node (ref "C63") (pin "2") (pinfunction "2_2") (pintype "passive"))
      (node (ref "C64") (pin "2") (pinfunction "2_2") (pintype "passive"))
      (node (ref "C65") (pin "2") (pinfunction "2_2") (pintype "passive"))
      (node (ref "C66") (pin "2") (pinfunction "2_2") (pintype "passive"))
      (node (ref "R68") (pin "2") (pinfunction "2_2") (pintype "passive"))
      (node (ref "R69") (pin "2") (pinfunction "2_2") (pintype "passive"))
      (node (ref "U20") (pin "1") (pinfunction "VDD1_1") (pintype "power_in"))
      (node (ref "U22") (pin "1") (pinfunction "VDD1_1") (pintype "power_in"))
      (node (ref "U24") (pin "1") (pinfunction "VDD1_1") (pintype "power_in"))
      (node (ref "U26") (pin "1") (pinfunction "VDD1_1") (pintype "power_in"))
    )
    (net (code "76") (name "unconnected-(LS1-NC-Pad2)") (class "Default")
      (node (ref "LS1") (pin "2") (pinfunction "NC_2") (pintype "passive"))
    )
    (net (code "77") (name "unconnected-(LS2-NC-Pad2)") (class "Default")
      (node (ref "LS2") (pin "2") (pinfunction "NC_2") (pintype "passive"))
    )
    (net (code "78") (name "unconnected-(U12-GND-Pad14)") (class "Default")
      (node (ref "U12") (pin "14") (pinfunction "GND_14") (pintype "passive"))
    )
  )
)
